# tinyRF.net
KiCad netlist of a schematic drawn in EAGLE
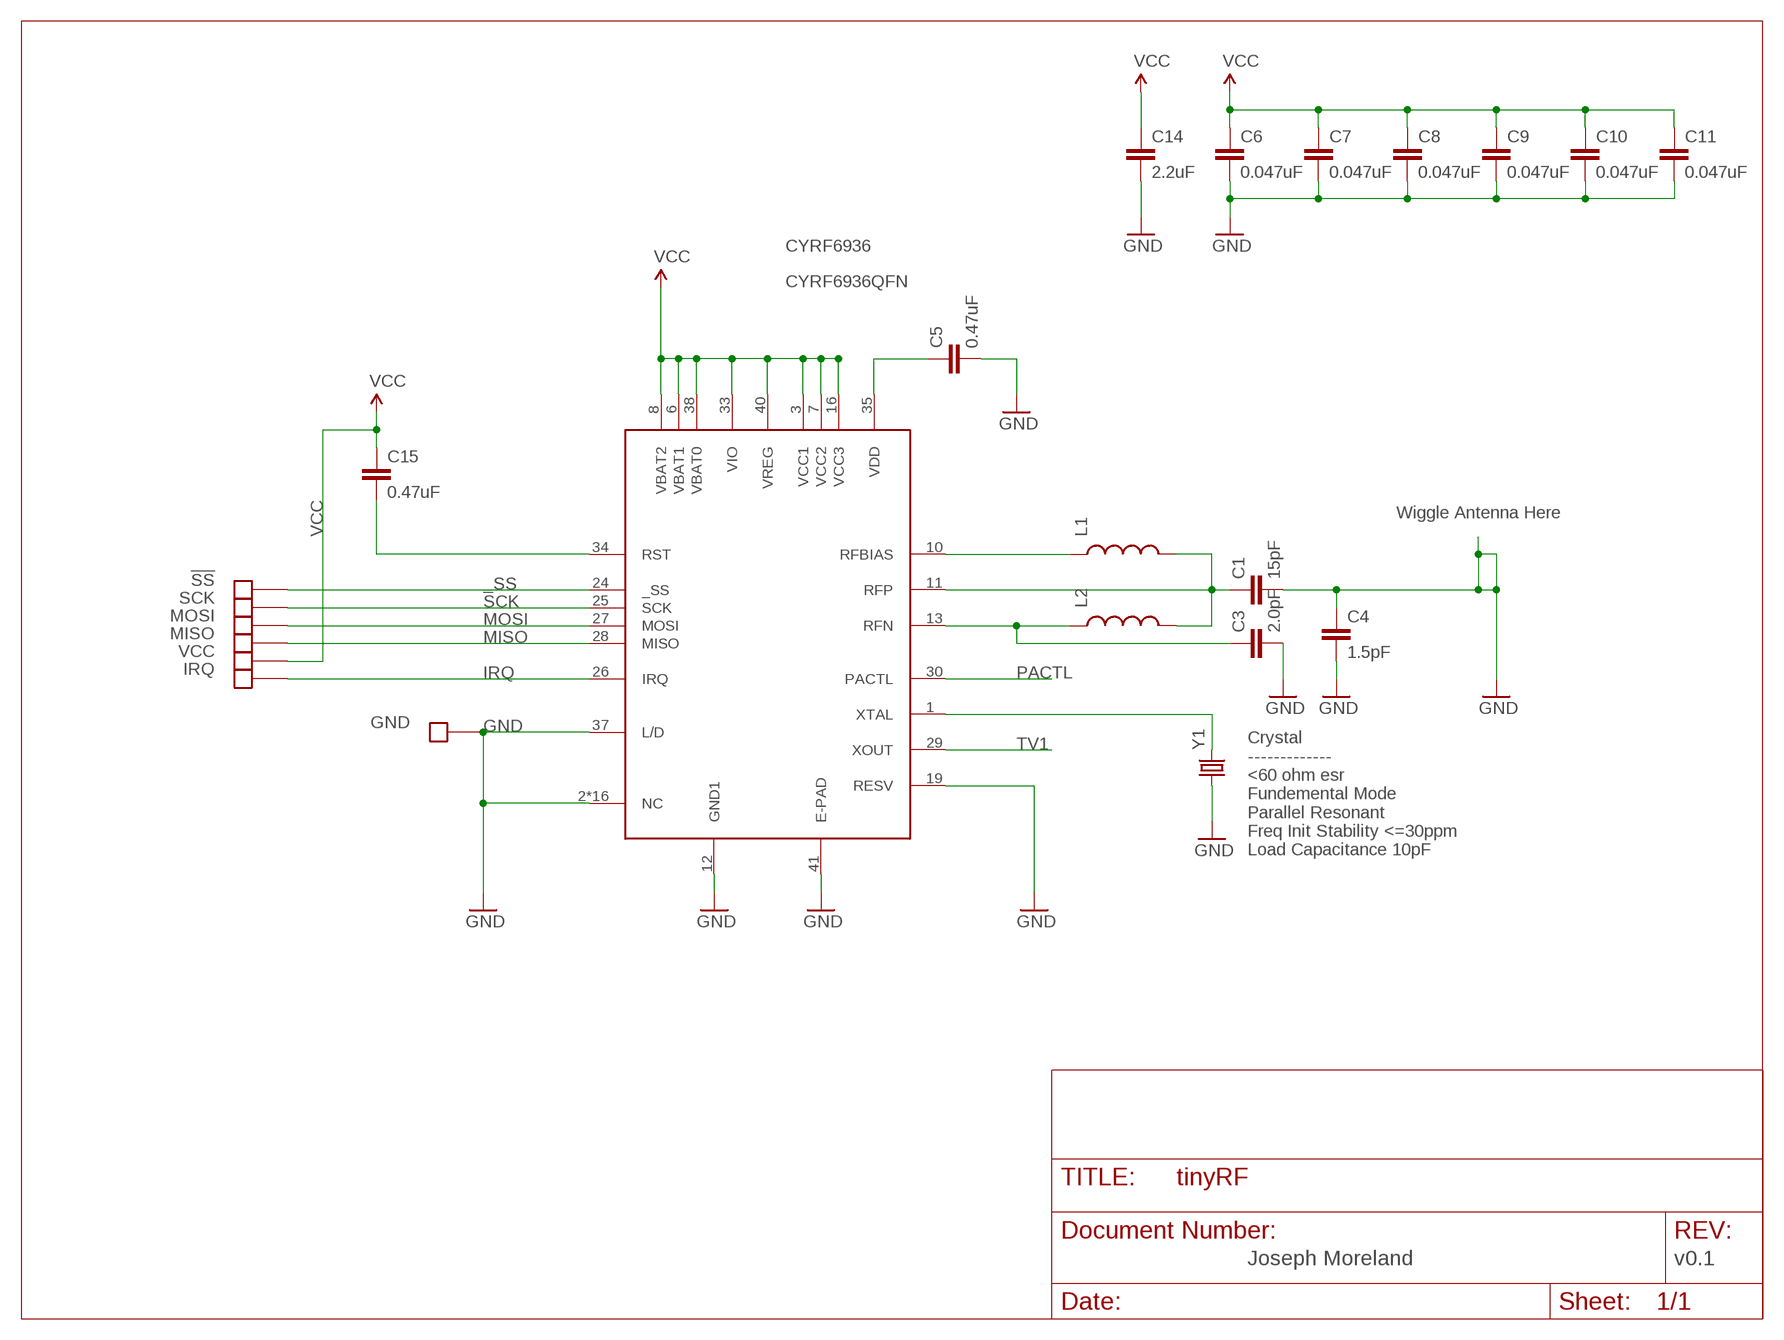
[diagram p0: schematic, sheet 1]

(export (version "E")
  (design (tool "Eeschema 10.0.6"))
  (components
    (comp (ref "!SS")
      (value "SOLDER_PADTH")
      (footprint "eagle-import:1X1_50MIL")
      (libsource (lib "eagle-import") (part "SOLDER_PADTH"))
    )
    (comp (ref "C1")
      (value "15pF")
      (footprint "eagle-import:0402-CAP")
      (fields (field (name "PARTNO") "C0402C150J5GACTU"))
      (libsource (lib "eagle-import") (part "CAP0402-CAP"))
    )
    (comp (ref "C3")
      (value "2.0pF")
      (footprint "eagle-import:0402-CAP")
      (fields (field (name "PARTNO") "C0402C209C5GACTU"))
      (libsource (lib "eagle-import") (part "CAP0402-CAP"))
    )
    (comp (ref "C4")
      (value "1.5pF")
      (footprint "eagle-import:0402-CAP")
      (fields (field (name "PARTNO") "C0402C159B5GACTU"))
      (libsource (lib "eagle-import") (part "CAP0402-CAP"))
    )
    (comp (ref "C5")
      (value "0.47uF")
      (footprint "eagle-import:0402-CAP")
      (fields (field (name "PARTNO") "GRM155R60J474KE19D"))
      (libsource (lib "eagle-import") (part "CAP0402-CAP"))
    )
    (comp (ref "C6")
      (value "0.047uF")
      (footprint "eagle-import:0402-CAP")
      (fields (field (name "PARTNO") "0402YD473KAT2A"))
      (libsource (lib "eagle-import") (part "CAP0402-CAP"))
    )
    (comp (ref "C7")
      (value "0.047uF")
      (footprint "eagle-import:0402-CAP")
      (fields (field (name "PARTNO") "0402YD473KAT2A"))
      (libsource (lib "eagle-import") (part "CAP0402-CAP"))
    )
    (comp (ref "C8")
      (value "0.047uF")
      (footprint "eagle-import:0402-CAP")
      (fields (field (name "PARTNO") "0402YD473KAT2A"))
      (libsource (lib "eagle-import") (part "CAP0402-CAP"))
    )
    (comp (ref "C9")
      (value "0.047uF")
      (footprint "eagle-import:0402-CAP")
      (fields (field (name "PARTNO") "0402YD473KAT2A"))
      (libsource (lib "eagle-import") (part "CAP0402-CAP"))
    )
    (comp (ref "C10")
      (value "0.047uF")
      (footprint "eagle-import:0402-CAP")
      (fields (field (name "PARTNO") "0402YD473KAT2A"))
      (libsource (lib "eagle-import") (part "CAP0402-CAP"))
    )
    (comp (ref "C11")
      (value "0.047uF")
      (footprint "eagle-import:0402-CAP")
      (fields (field (name "PARTNO") "0402YD473KAT2A"))
      (libsource (lib "eagle-import") (part "CAP0402-CAP"))
    )
    (comp (ref "C14")
      (value "2.2uF")
      (footprint "eagle-import:0805")
      (fields (field (name "PARTNO") "GRM21BR71A225KA01L"))
      (libsource (lib "eagle-import") (part "CAP0805"))
    )
    (comp (ref "C15")
      (value "0.47uF")
      (footprint "eagle-import:0402-CAP")
      (fields (field (name "PARTNO") "GRM155R60J474KE19D"))
      (libsource (lib "eagle-import") (part "CAP0402-CAP"))
    )
    (comp (ref "CYRF6936")
      (value "CYRF6936QFN")
      (footprint "eagle-import:QFN50P600X600X90-41N")
      (fields (field (name "PARTNO") "CYRF6936B-40LTXC"))
      (libsource (lib "eagle-import") (part "CYRF6936QFN"))
    )
    (comp (ref "GND")
      (value "SOLDER_PADTH")
      (footprint "eagle-import:1X1_50MIL")
      (libsource (lib "eagle-import") (part "SOLDER_PADTH"))
    )
    (comp (ref "IRQ")
      (value "SOLDER_PADTH")
      (footprint "eagle-import:1X1_50MIL")
      (libsource (lib "eagle-import") (part "SOLDER_PADTH"))
    )
    (comp (ref "L1")
      (value "INDUCTOR0603")
      (footprint "eagle-import:0603")
      (fields (field (name "PARTNO") "ELJ-RE22NGFA"))
      (libsource (lib "eagle-import") (part "INDUCTOR0603"))
    )
    (comp (ref "L2")
      (value "INDUCTOR0402")
      (footprint "eagle-import:C0402")
      (fields (field (name "PARTNO") "ELJ-RF1N8DFB"))
      (libsource (lib "eagle-import") (part "INDUCTOR0402"))
    )
    (comp (ref "MISO")
      (value "SOLDER_PADTH")
      (footprint "eagle-import:1X1_50MIL")
      (libsource (lib "eagle-import") (part "SOLDER_PADTH"))
    )
    (comp (ref "MOSI")
      (value "SOLDER_PADTH")
      (footprint "eagle-import:1X1_50MIL")
      (libsource (lib "eagle-import") (part "SOLDER_PADTH"))
    )
    (comp (ref "SCK")
      (value "SOLDER_PADTH")
      (footprint "eagle-import:1X1_50MIL")
      (libsource (lib "eagle-import") (part "SOLDER_PADTH"))
    )
    (comp (ref "VCC")
      (value "SOLDER_PADTH")
      (footprint "eagle-import:1X1_50MIL")
      (libsource (lib "eagle-import") (part "SOLDER_PADTH"))
    )
    (comp (ref "Y1")
      (value "CRYSTAL5X3")
      (footprint "eagle-import:CRYSTAL-SMD-5X3")
      (fields (field (name "PARTNO") "7B-12.000MEEQ-T"))
      (libsource (lib "eagle-import") (part "CRYSTAL5X3"))
    )
  )
  (nets
    (net (code "1") (name "/IRQ") (class "Default")
      (node (ref "CYRF6936") (pin "26") (pinfunction "IRQ_26") (pintype "bidirectional"))
      (node (ref "IRQ") (pin "1") (pinfunction "NET_1") (pintype "bidirectional"))
    )
    (net (code "2") (name "/MISO") (class "Default")
      (node (ref "CYRF6936") (pin "28") (pinfunction "MISO_28") (pintype "bidirectional"))
      (node (ref "MISO") (pin "1") (pinfunction "NET_1") (pintype "bidirectional"))
    )
    (net (code "3") (name "/MOSI") (class "Default")
      (node (ref "CYRF6936") (pin "27") (pinfunction "MOSI_27") (pintype "bidirectional"))
      (node (ref "MOSI") (pin "1") (pinfunction "NET_1") (pintype "bidirectional"))
    )
    (net (code "4") (name "/PACTL") (class "Default")
      (node (ref "CYRF6936") (pin "30") (pinfunction "PACTL_30") (pintype "bidirectional"))
    )
    (net (code "5") (name "/SCK") (class "Default")
      (node (ref "CYRF6936") (pin "25") (pinfunction "SCK_25") (pintype "bidirectional"))
      (node (ref "SCK") (pin "1") (pinfunction "NET_1") (pintype "bidirectional"))
    )
    (net (code "6") (name "/TV1") (class "Default")
      (node (ref "CYRF6936") (pin "29") (pinfunction "XOUT_29") (pintype "bidirectional"))
    )
    (net (code "7") (name "/_SS") (class "Default")
      (node (ref "!SS") (pin "1") (pinfunction "NET_1") (pintype "bidirectional"))
      (node (ref "CYRF6936") (pin "24") (pinfunction "_SS_24") (pintype "bidirectional"))
    )
    (net (code "8") (name "GND") (class "Default")
      (node (ref "C1") (pin "2") (pinfunction "2_2") (pintype "passive"))
      (node (ref "C10") (pin "2") (pinfunction "2_2") (pintype "passive"))
      (node (ref "C11") (pin "2") (pinfunction "2_2") (pintype "passive"))
      (node (ref "C14") (pin "2") (pinfunction "2_2") (pintype "passive"))
      (node (ref "C3") (pin "2") (pinfunction "2_2") (pintype "passive"))
      (node (ref "C4") (pin "1") (pinfunction "1_1") (pintype "passive"))
      (node (ref "C4") (pin "2") (pinfunction "2_2") (pintype "passive"))
      (node (ref "C5") (pin "2") (pinfunction "2_2") (pintype "passive"))
      (node (ref "C6") (pin "2") (pinfunction "2_2") (pintype "passive"))
      (node (ref "C7") (pin "2") (pinfunction "2_2") (pintype "passive"))
      (node (ref "C8") (pin "2") (pinfunction "2_2") (pintype "passive"))
      (node (ref "C9") (pin "2") (pinfunction "2_2") (pintype "passive"))
      (node (ref "CYRF6936") (pin "12") (pinfunction "GND1_12") (pintype "bidirectional"))
      (node (ref "CYRF6936") (pin "14") (pinfunction "NC_14") (pintype "bidirectional"))
      (node (ref "CYRF6936") (pin "15") (pinfunction "NC_15") (pintype "bidirectional"))
      (node (ref "CYRF6936") (pin "17") (pinfunction "NC_17") (pintype "bidirectional"))
      (node (ref "CYRF6936") (pin "18") (pinfunction "NC_18") (pintype "bidirectional"))
      (node (ref "CYRF6936") (pin "19") (pinfunction "RESV_19") (pintype "bidirectional"))
      (node (ref "CYRF6936") (pin "2") (pinfunction "NC_2") (pintype "bidirectional"))
      (node (ref "CYRF6936") (pin "20") (pinfunction "NC_20") (pintype "bidirectional"))
      (node (ref "CYRF6936") (pin "21") (pinfunction "NC_21") (pintype "bidirectional"))
      (node (ref "CYRF6936") (pin "22") (pinfunction "NC_22") (pintype "bidirectional"))
      (node (ref "CYRF6936") (pin "23") (pinfunction "NC_23") (pintype "bidirectional"))
      (node (ref "CYRF6936") (pin "31") (pinfunction "NC_31") (pintype "bidirectional"))
      (node (ref "CYRF6936") (pin "32") (pinfunction "NC_32") (pintype "bidirectional"))
      (node (ref "CYRF6936") (pin "36") (pinfunction "NC_36") (pintype "bidirectional"))
      (node (ref "CYRF6936") (pin "37") (pinfunction "L/D_37") (pintype "bidirectional"))
      (node (ref "CYRF6936") (pin "39") (pinfunction "NC_39") (pintype "bidirectional"))
      (node (ref "CYRF6936") (pin "4") (pinfunction "NC_4") (pintype "bidirectional"))
      (node (ref "CYRF6936") (pin "41") (pinfunction "E-PAD_41") (pintype "bidirectional"))
      (node (ref "CYRF6936") (pin "5") (pinfunction "NC_5") (pintype "bidirectional"))
      (node (ref "CYRF6936") (pin "9") (pinfunction "NC_9") (pintype "bidirectional"))
      (node (ref "GND") (pin "1") (pinfunction "NET_1") (pintype "bidirectional"))
      (node (ref "Y1") (pin "1") (pinfunction "1_1") (pintype "passive"))
    )
    (net (code "9") (name "Net-(CYRF6936-RFBIAS)") (class "Default")
      (node (ref "CYRF6936") (pin "10") (pinfunction "RFBIAS_10") (pintype "bidirectional"))
      (node (ref "L1") (pin "1") (pinfunction "1_1") (pintype "passive"))
    )
    (net (code "10") (name "Net-(CYRF6936-RFN)") (class "Default")
      (node (ref "C3") (pin "1") (pinfunction "1_1") (pintype "passive"))
      (node (ref "CYRF6936") (pin "13") (pinfunction "RFN_13") (pintype "bidirectional"))
      (node (ref "L2") (pin "1") (pinfunction "1_1") (pintype "passive"))
    )
    (net (code "11") (name "Net-(CYRF6936-RFP)") (class "Default")
      (node (ref "C1") (pin "1") (pinfunction "1_1") (pintype "passive"))
      (node (ref "CYRF6936") (pin "11") (pinfunction "RFP_11") (pintype "bidirectional"))
      (node (ref "L1") (pin "2") (pinfunction "2_2") (pintype "passive"))
      (node (ref "L2") (pin "2") (pinfunction "2_2") (pintype "passive"))
    )
    (net (code "12") (name "Net-(CYRF6936-RST)") (class "Default")
      (node (ref "C15") (pin "2") (pinfunction "2_2") (pintype "passive"))
      (node (ref "CYRF6936") (pin "34") (pinfunction "RST_34") (pintype "bidirectional"))
    )
    (net (code "13") (name "Net-(CYRF6936-VDD)") (class "Default")
      (node (ref "C5") (pin "1") (pinfunction "1_1") (pintype "passive"))
      (node (ref "CYRF6936") (pin "35") (pinfunction "VDD_35") (pintype "bidirectional"))
    )
    (net (code "14") (name "Net-(CYRF6936-XTAL)") (class "Default")
      (node (ref "CYRF6936") (pin "1") (pinfunction "XTAL_1") (pintype "bidirectional"))
      (node (ref "Y1") (pin "3") (pinfunction "2_3") (pintype "passive"))
    )
    (net (code "15") (name "VCC") (class "Default")
      (node (ref "C10") (pin "1") (pinfunction "1_1") (pintype "passive"))
      (node (ref "C11") (pin "1") (pinfunction "1_1") (pintype "passive"))
      (node (ref "C14") (pin "1") (pinfunction "1_1") (pintype "passive"))
      (node (ref "C15") (pin "1") (pinfunction "1_1") (pintype "passive"))
      (node (ref "C6") (pin "1") (pinfunction "1_1") (pintype "passive"))
      (node (ref "C7") (pin "1") (pinfunction "1_1") (pintype "passive"))
      (node (ref "C8") (pin "1") (pinfunction "1_1") (pintype "passive"))
      (node (ref "C9") (pin "1") (pinfunction "1_1") (pintype "passive"))
      (node (ref "CYRF6936") (pin "16") (pinfunction "VCC3_16") (pintype "bidirectional"))
      (node (ref "CYRF6936") (pin "3") (pinfunction "VCC1_3") (pintype "bidirectional"))
      (node (ref "CYRF6936") (pin "33") (pinfunction "VIO_33") (pintype "bidirectional"))
      (node (ref "CYRF6936") (pin "38") (pinfunction "VBAT0_38") (pintype "bidirectional"))
      (node (ref "CYRF6936") (pin "40") (pinfunction "VREG_40") (pintype "bidirectional"))
      (node (ref "CYRF6936") (pin "6") (pinfunction "VBAT1_6") (pintype "bidirectional"))
      (node (ref "CYRF6936") (pin "7") (pinfunction "VCC2_7") (pintype "bidirectional"))
      (node (ref "CYRF6936") (pin "8") (pinfunction "VBAT2_8") (pintype "bidirectional"))
      (node (ref "VCC") (pin "1") (pinfunction "NET_1") (pintype "bidirectional"))
    )
  )
)
